# CAR_Amplifier.net
KiCad netlist of a schematic drawn in Altium Designer
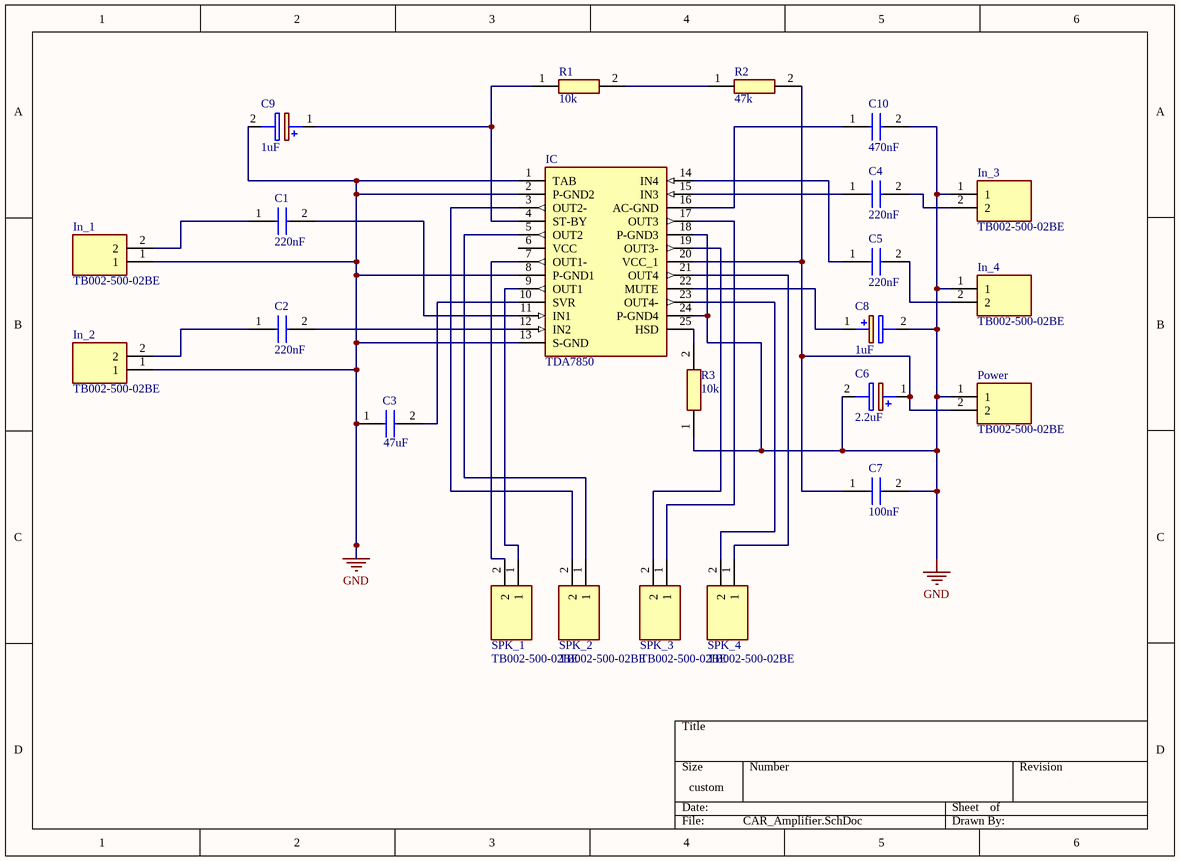
[diagram p0: CAR_Amplifier.SchDoc]

(export (version "E")
  (design (tool "Eeschema 10.0.6"))
  (components
    (comp (ref "C1")
      (value "220nF")
      (footprint "SamacSys:C1210_FT")
      (description "Capacitor")
      (fields
        (field (name "MANUFACTURER_PART_NUMBER") "C1210X224KARACAUTO")
        (field (name "MOUSER PART NUMBER") "80-C1210X224KARAUTO")
      )
      (libsource (lib "CAR_Amplifier") (part "C1210X224KARACAUTO"))
    )
    (comp (ref "C2")
      (value "220nF")
      (footprint "SamacSys:C1210_FT")
      (description "Capacitor")
      (fields
        (field (name "MANUFACTURER_PART_NUMBER") "C1210X224KARACAUTO")
        (field (name "MOUSER PART NUMBER") "80-C1210X224KARAUTO")
      )
      (libsource (lib "CAR_Amplifier") (part "C1210X224KARACAUTO"))
    )
    (comp (ref "C3")
      (value "47uF")
      (footprint "SamacSys:FK20")
      (description "Capacitor")
      (fields (field (name "MANUFACTURER_PART_NUMBER") "FK20X5R0J476MN000"))
      (libsource (lib "CAR_Amplifier") (part "FK20X5R0J476MN000"))
    )
    (comp (ref "C4")
      (value "220nF")
      (footprint "SamacSys:C1210_FT")
      (description "Capacitor")
      (fields
        (field (name "MANUFACTURER_PART_NUMBER") "C1210X224KARACAUTO")
        (field (name "MOUSER PART NUMBER") "80-C1210X224KARAUTO")
      )
      (libsource (lib "CAR_Amplifier") (part "C1210X224KARACAUTO"))
    )
    (comp (ref "C5")
      (value "220nF")
      (footprint "SamacSys:C1210_FT")
      (description "Capacitor")
      (fields
        (field (name "MANUFACTURER_PART_NUMBER") "C1210X224KARACAUTO")
        (field (name "MOUSER PART NUMBER") "80-C1210X224KARAUTO")
      )
      (libsource (lib "CAR_Amplifier") (part "C1210X224KARACAUTO"))
    )
    (comp (ref "C6")
      (value "2.2uF")
      (footprint "SamacSys:CAPAE420X610N")
      (description "Capacitor Polarised")
      (fields (field (name "MANUFACTURER_PART_NUMBER") "UWD1H2R2MCL1GS"))
      (libsource (lib "CAR_Amplifier") (part "UWD1H2R2MCL1GS"))
    )
    (comp (ref "C7")
      (value "100nF")
      (footprint "SamacSys:CAPPA1420W55L380D260")
      (description "Capacitor")
      (fields
        (field (name "MANUFACTURER_PART_NUMBER") "A104K15X7RF5UAAP")
        (field (name "MOUSER PART NUMBER") "594-A104K15X7RF5UAAP")
      )
      (libsource (lib "CAR_Amplifier") (part "A104K15X7RF5UAAP"))
    )
    (comp (ref "C8")
      (value "1uF")
      (footprint "SamacSys:CAPAE430X550N")
      (description "Capacitor Polarised")
      (fields
        (field (name "MANUFACTURER_PART_NUMBER") "865080640001")
        (field (name "MOUSER PART NUMBER") "710-865080640001")
      )
      (libsource (lib "") (part "865080640001_1"))
    )
    (comp (ref "C9")
      (value "1uF")
      (footprint "SamacSys:CAPAE430X550N")
      (description "Capacitor Polarised")
      (fields
        (field (name "MANUFACTURER_PART_NUMBER") "865080640001")
        (field (name "MOUSER PART NUMBER") "710-865080640001")
      )
      (libsource (lib "CAR_Amplifier") (part "865080640001"))
    )
    (comp (ref "C10")
      (value "470nF")
      (footprint "SamacSys:C1206")
      (description "Capacitor")
      (fields
        (field (name "MANUFACTURER_PART_NUMBER") "C1206C474K1REC7210")
        (field (name "MOUSER PART NUMBER") "80-C1206C474K1RECLR")
      )
      (libsource (lib "CAR_Amplifier") (part "C1206C474K1REC7210"))
    )
    (comp (ref "IC")
      (value "TDA7850")
      (footprint "SamacSys:TO100P465X2910X1977-25P")
      (description "Integrated Circuit")
      (fields (field (name "MOUSER PART NUMBER") "511-TDA7850"))
      (libsource (lib "CAR_Amplifier") (part "TDA7850"))
    )
    (comp (ref "In_1")
      (value "TB002-500-02BE")
      (footprint "SamacSys:TB00250002BE")
      (description "Connector")
      (fields (field (name "MOUSER PART NUMBER") "490-TB002-500-02BE"))
      (libsource (lib "CAR_Amplifier") (part "TB002-500-02BE"))
    )
    (comp (ref "In_2")
      (value "TB002-500-02BE")
      (footprint "SamacSys:TB00250002BE")
      (description "Connector")
      (fields (field (name "MOUSER PART NUMBER") "490-TB002-500-02BE"))
      (libsource (lib "CAR_Amplifier") (part "TB002-500-02BE"))
    )
    (comp (ref "In_3")
      (value "TB002-500-02BE")
      (footprint "SamacSys:TB00250002BE")
      (description "Connector")
      (fields (field (name "MOUSER PART NUMBER") "490-TB002-500-02BE"))
      (libsource (lib "") (part "TB002-500-02BE_1"))
    )
    (comp (ref "In_4")
      (value "TB002-500-02BE")
      (footprint "SamacSys:TB00250002BE")
      (description "Connector")
      (fields (field (name "MOUSER PART NUMBER") "490-TB002-500-02BE"))
      (libsource (lib "") (part "TB002-500-02BE_1"))
    )
    (comp (ref "Power")
      (value "TB002-500-02BE")
      (footprint "SamacSys:TB00250002BE")
      (description "Connector")
      (fields (field (name "MOUSER PART NUMBER") "490-TB002-500-02BE"))
      (libsource (lib "") (part "TB002-500-02BE_1"))
    )
    (comp (ref "R1")
      (value "10k")
      (footprint "SamacSys:RESC1608X55N")
      (description "Resistor")
      (fields
        (field (name "MANUFACTURER_PART_NUMBER") "MCT06030D1002DP500")
        (field (name "MOUSER PART NUMBER") "594-MCT06030D1002DP5")
      )
      (libsource (lib "") (part "MCT06030D1002DP500_1"))
    )
    (comp (ref "R2")
      (value "47k")
      (footprint "SamacSys:RESC1608X55N")
      (description "Resistor")
      (fields
        (field (name "MANUFACTURER_PART_NUMBER") "MCT06030C4702FP500")
        (field (name "MOUSER PART NUMBER") "594-MCT06030C4702FP5")
      )
      (libsource (lib "CAR_Amplifier") (part "MCT06030C4702FP500"))
    )
    (comp (ref "R3")
      (value "10k")
      (footprint "SamacSys:RESC1608X55N")
      (description "Resistor")
      (fields
        (field (name "MANUFACTURER_PART_NUMBER") "MCT06030D1002DP500")
        (field (name "MOUSER PART NUMBER") "594-MCT06030D1002DP5")
      )
      (libsource (lib "CAR_Amplifier") (part "MCT06030D1002DP500"))
    )
    (comp (ref "SPK_1")
      (value "TB002-500-02BE")
      (footprint "SamacSys:TB00250002BE")
      (description "Connector")
      (fields (field (name "MOUSER PART NUMBER") "490-TB002-500-02BE"))
      (libsource (lib "") (part "TB002-500-02BE_2"))
    )
    (comp (ref "SPK_2")
      (value "TB002-500-02BE")
      (footprint "SamacSys:TB00250002BE")
      (description "Connector")
      (fields (field (name "MOUSER PART NUMBER") "490-TB002-500-02BE"))
      (libsource (lib "") (part "TB002-500-02BE_2"))
    )
    (comp (ref "SPK_3")
      (value "TB002-500-02BE")
      (footprint "SamacSys:TB00250002BE")
      (description "Connector")
      (fields (field (name "MOUSER PART NUMBER") "490-TB002-500-02BE"))
      (libsource (lib "") (part "TB002-500-02BE_2"))
    )
    (comp (ref "SPK_4")
      (value "TB002-500-02BE")
      (footprint "SamacSys:TB00250002BE")
      (description "Connector")
      (fields (field (name "MOUSER PART NUMBER") "490-TB002-500-02BE"))
      (libsource (lib "") (part "TB002-500-02BE_2"))
    )
  )
  (nets
    (net (code "1") (name "GND") (class "Default")
      (node (ref "C10") (pin "2") (pinfunction "2_2") (pintype "passive"))
      (node (ref "C3") (pin "1") (pinfunction "1_1") (pintype "passive"))
      (node (ref "C6") (pin "2") (pinfunction "-_2") (pintype "passive"))
      (node (ref "C7") (pin "2") (pinfunction "-_2") (pintype "passive"))
      (node (ref "C8") (pin "2") (pinfunction "-_2") (pintype "passive"))
      (node (ref "C9") (pin "2") (pinfunction "-_2") (pintype "passive"))
      (node (ref "IC") (pin "1") (pinfunction "TAB_1") (pintype "passive"))
      (node (ref "IC") (pin "13") (pinfunction "S-GND_13") (pintype "power_in"))
      (node (ref "IC") (pin "18") (pinfunction "P-GND3_18") (pintype "power_in"))
      (node (ref "IC") (pin "2") (pinfunction "P-GND2_2") (pintype "power_in"))
      (node (ref "IC") (pin "24") (pinfunction "P-GND4_24") (pintype "power_in"))
      (node (ref "IC") (pin "8") (pinfunction "P-GND1_8") (pintype "power_in"))
      (node (ref "In_1") (pin "1") (pinfunction "1_1") (pintype "passive"))
      (node (ref "In_2") (pin "1") (pinfunction "1_1") (pintype "passive"))
      (node (ref "In_3") (pin "1") (pinfunction "1_1") (pintype "passive"))
      (node (ref "In_4") (pin "1") (pinfunction "1_1") (pintype "passive"))
      (node (ref "Power") (pin "1") (pinfunction "1_1") (pintype "passive"))
      (node (ref "R3") (pin "1") (pinfunction "1_1") (pintype "passive"))
    )
    (net (code "2") (name "Net-(C1-Pad1)") (class "Default")
      (node (ref "C1") (pin "1") (pinfunction "1_1") (pintype "passive"))
      (node (ref "In_1") (pin "2") (pinfunction "2_2") (pintype "passive"))
    )
    (net (code "3") (name "Net-(C2-Pad1)") (class "Default")
      (node (ref "C2") (pin "1") (pinfunction "1_1") (pintype "passive"))
      (node (ref "In_2") (pin "2") (pinfunction "2_2") (pintype "passive"))
    )
    (net (code "4") (name "Net-(C4-Pad2)") (class "Default")
      (node (ref "C4") (pin "2") (pinfunction "2_2") (pintype "passive"))
      (node (ref "In_3") (pin "2") (pinfunction "2_2") (pintype "passive"))
    )
    (net (code "5") (name "Net-(C5-Pad2)") (class "Default")
      (node (ref "C5") (pin "2") (pinfunction "2_2") (pintype "passive"))
      (node (ref "In_4") (pin "2") (pinfunction "2_2") (pintype "passive"))
    )
    (net (code "6") (name "Net-(C6-+)") (class "Default")
      (node (ref "C6") (pin "1") (pinfunction "+_1") (pintype "passive"))
      (node (ref "C7") (pin "1") (pinfunction "+_1") (pintype "passive"))
      (node (ref "IC") (pin "20") (pinfunction "VCC_1_20") (pintype "power_in"))
      (node (ref "Power") (pin "2") (pinfunction "2_2") (pintype "passive"))
      (node (ref "R2") (pin "2") (pinfunction "2_2") (pintype "passive"))
    )
    (net (code "7") (name "Net-(C8-+)") (class "Default")
      (node (ref "C8") (pin "1") (pinfunction "+_1") (pintype "passive"))
      (node (ref "IC") (pin "22") (pinfunction "MUTE_22") (pintype "passive"))
    )
    (net (code "8") (name "Net-(C9-+)") (class "Default")
      (node (ref "C9") (pin "1") (pinfunction "+_1") (pintype "passive"))
      (node (ref "IC") (pin "4") (pinfunction "ST-BY_4") (pintype "passive"))
      (node (ref "R1") (pin "1") (pinfunction "1_1") (pintype "passive"))
    )
    (net (code "9") (name "Net-(IC-AC-GND)") (class "Default")
      (node (ref "C10") (pin "1") (pinfunction "1_1") (pintype "passive"))
      (node (ref "IC") (pin "16") (pinfunction "AC-GND_16") (pintype "power_in"))
    )
    (net (code "10") (name "Net-(IC-HSD)") (class "Default")
      (node (ref "IC") (pin "25") (pinfunction "HSD_25") (pintype "passive"))
      (node (ref "R3") (pin "2") (pinfunction "2_2") (pintype "passive"))
    )
    (net (code "11") (name "Net-(IC-IN1)") (class "Default")
      (node (ref "C1") (pin "2") (pinfunction "2_2") (pintype "passive"))
      (node (ref "IC") (pin "11") (pinfunction "IN1_11") (pintype "input"))
    )
    (net (code "12") (name "Net-(IC-IN2)") (class "Default")
      (node (ref "C2") (pin "2") (pinfunction "2_2") (pintype "passive"))
      (node (ref "IC") (pin "12") (pinfunction "IN2_12") (pintype "input"))
    )
    (net (code "13") (name "Net-(IC-IN3)") (class "Default")
      (node (ref "C4") (pin "1") (pinfunction "1_1") (pintype "passive"))
      (node (ref "IC") (pin "15") (pinfunction "IN3_15") (pintype "input"))
    )
    (net (code "14") (name "Net-(IC-IN4)") (class "Default")
      (node (ref "C5") (pin "1") (pinfunction "1_1") (pintype "passive"))
      (node (ref "IC") (pin "14") (pinfunction "IN4_14") (pintype "input"))
    )
    (net (code "15") (name "Net-(IC-OUT1)") (class "Default")
      (node (ref "IC") (pin "9") (pinfunction "OUT1_9") (pintype "output"))
      (node (ref "SPK_1") (pin "1") (pinfunction "1_1") (pintype "passive"))
    )
    (net (code "16") (name "Net-(IC-OUT1-)") (class "Default")
      (node (ref "IC") (pin "7") (pinfunction "OUT1-_7") (pintype "output"))
      (node (ref "SPK_1") (pin "2") (pinfunction "2_2") (pintype "passive"))
    )
    (net (code "17") (name "Net-(IC-OUT2)") (class "Default")
      (node (ref "IC") (pin "5") (pinfunction "OUT2_5") (pintype "output"))
      (node (ref "SPK_2") (pin "1") (pinfunction "1_1") (pintype "passive"))
    )
    (net (code "18") (name "Net-(IC-OUT2-)") (class "Default")
      (node (ref "IC") (pin "3") (pinfunction "OUT2-_3") (pintype "output"))
      (node (ref "SPK_2") (pin "2") (pinfunction "2_2") (pintype "passive"))
    )
    (net (code "19") (name "Net-(IC-OUT3)") (class "Default")
      (node (ref "IC") (pin "17") (pinfunction "OUT3_17") (pintype "output"))
      (node (ref "SPK_3") (pin "1") (pinfunction "1_1") (pintype "passive"))
    )
    (net (code "20") (name "Net-(IC-OUT3-)") (class "Default")
      (node (ref "IC") (pin "19") (pinfunction "OUT3-_19") (pintype "output"))
      (node (ref "SPK_3") (pin "2") (pinfunction "2_2") (pintype "passive"))
    )
    (net (code "21") (name "Net-(IC-OUT4)") (class "Default")
      (node (ref "IC") (pin "21") (pinfunction "OUT4_21") (pintype "output"))
      (node (ref "SPK_4") (pin "1") (pinfunction "1_1") (pintype "passive"))
    )
    (net (code "22") (name "Net-(IC-OUT4-)") (class "Default")
      (node (ref "IC") (pin "23") (pinfunction "OUT4-_23") (pintype "output"))
      (node (ref "SPK_4") (pin "2") (pinfunction "2_2") (pintype "passive"))
    )
    (net (code "23") (name "Net-(IC-SVR)") (class "Default")
      (node (ref "C3") (pin "2") (pinfunction "2_2") (pintype "passive"))
      (node (ref "IC") (pin "10") (pinfunction "SVR_10") (pintype "passive"))
    )
    (net (code "24") (name "Net-(R1-Pad2)") (class "Default")
      (node (ref "R1") (pin "2") (pinfunction "2_2") (pintype "passive"))
      (node (ref "R2") (pin "1") (pinfunction "1_1") (pintype "passive"))
    )
    (net (code "25") (name "unconnected-(IC-VCC-Pad6)") (class "Default")
      (node (ref "IC") (pin "6") (pinfunction "VCC_6") (pintype "power_in"))
    )
  )
)
